# elektrosluch.net
KiCad netlist of a schematic drawn in EAGLE
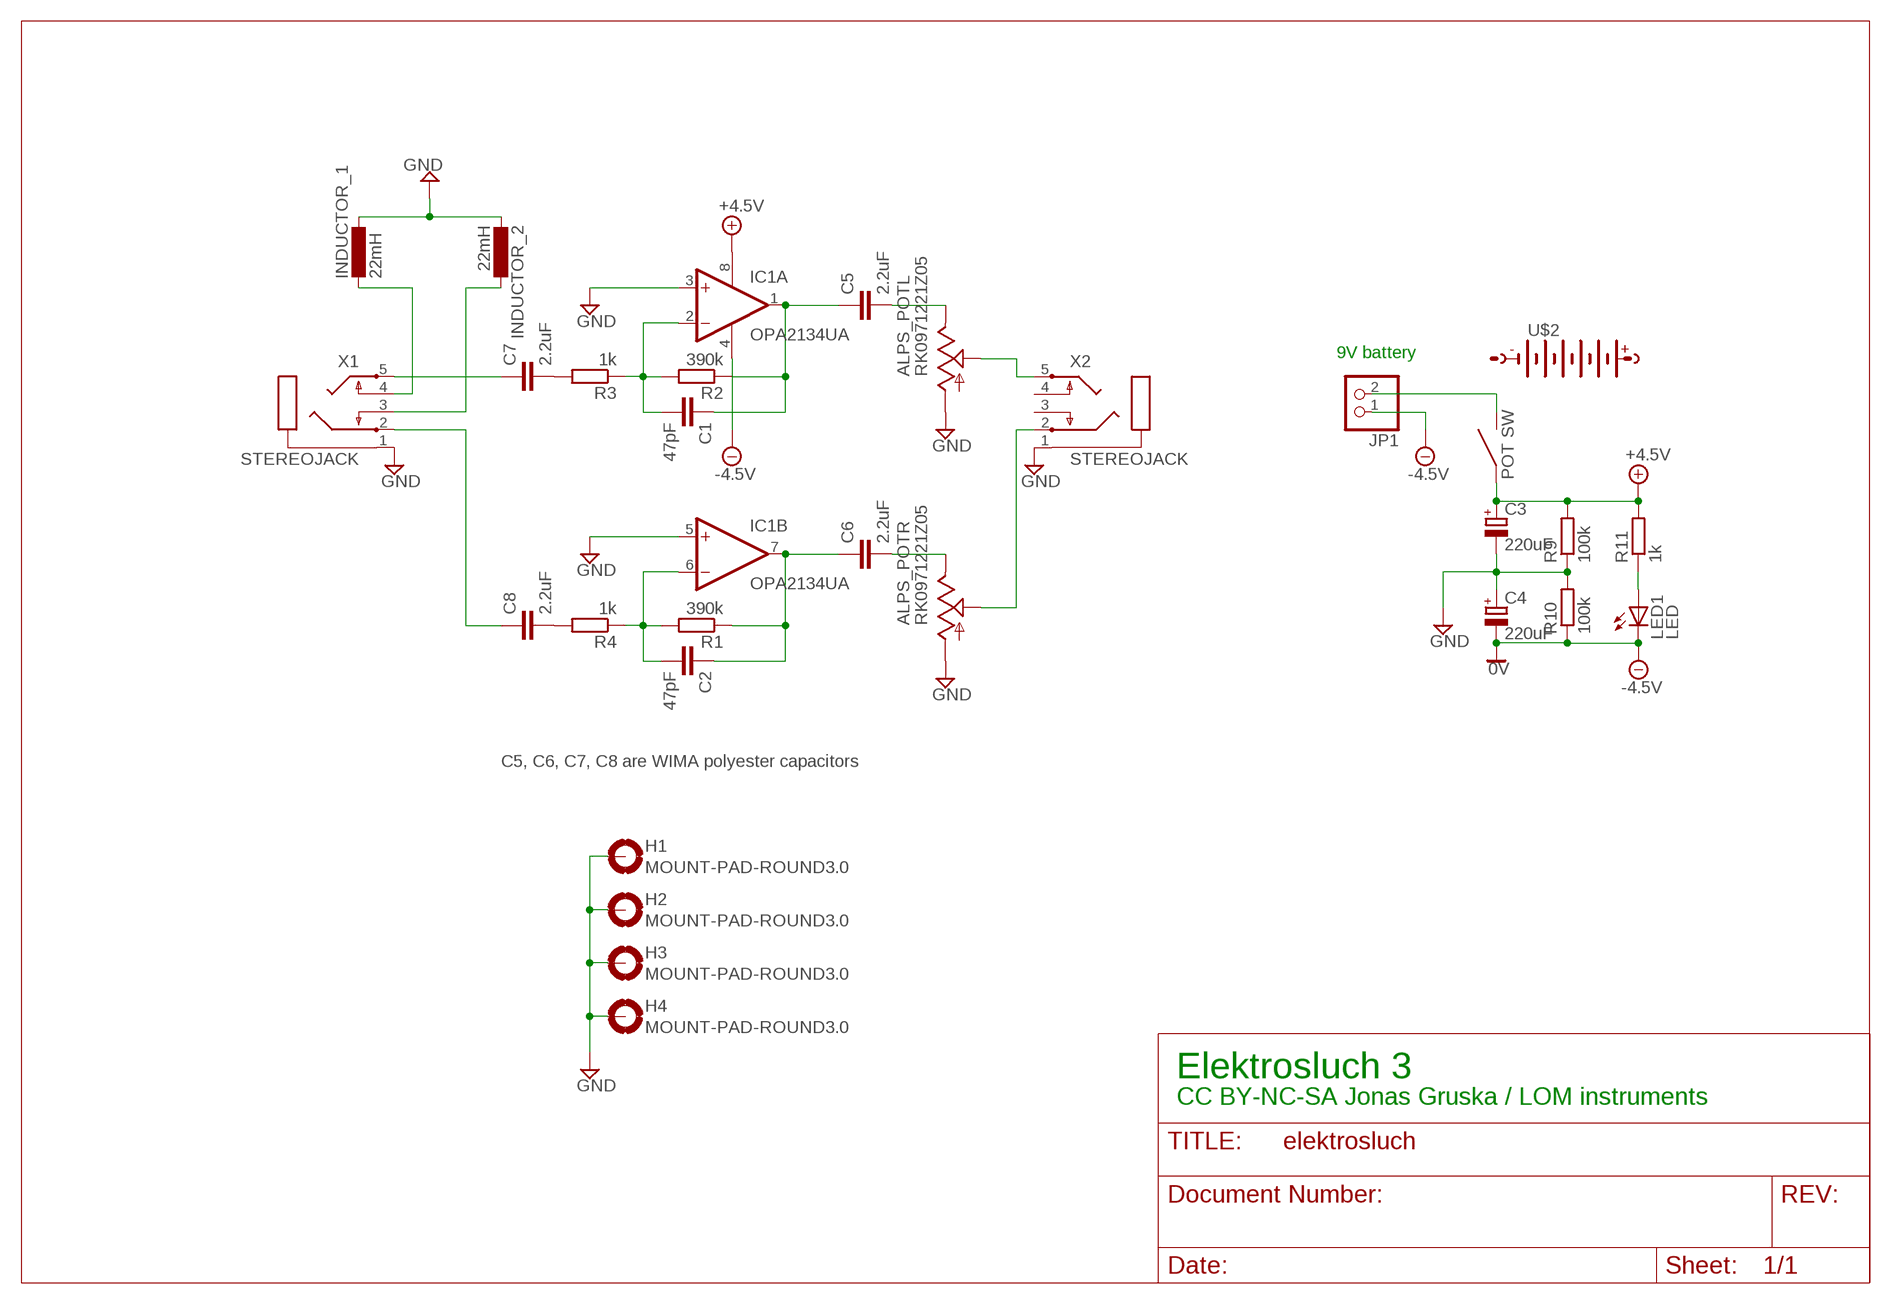
[diagram p0: schematic, sheet 1]

(export (version "E")
  (design (tool "Eeschema 10.0.6"))
  (components
    (comp (ref "ALPS_POT")
      (value "RK0971221Z05")
      (footprint "eagle-import:ALPS_RK0971221Z0X")
      (libsource (lib "eagle-import") (part "ALPS_RK0971221Z0N"))
    )
    (comp (ref "C1")
      (value "47pF")
      (footprint "eagle-import:C0805")
      (libsource (lib "eagle-import") (part "C-EUC0805"))
    )
    (comp (ref "C2")
      (value "47pF")
      (footprint "eagle-import:C0805")
      (libsource (lib "eagle-import") (part "C-EUC0805"))
    )
    (comp (ref "C3")
      (value "220uF")
      (footprint "eagle-import:PANASONIC_D")
      (libsource (lib "eagle-import") (part "CPOL-EUD"))
    )
    (comp (ref "C4")
      (value "220uF")
      (footprint "eagle-import:PANASONIC_D")
      (libsource (lib "eagle-import") (part "CPOL-EUD"))
    )
    (comp (ref "C5")
      (value "2.2uF")
      (footprint "eagle-import:WIMA10UF")
      (libsource (lib "eagle-import") (part "WIMA10UF"))
    )
    (comp (ref "C6")
      (value "2.2uF")
      (footprint "eagle-import:WIMA10UF")
      (libsource (lib "eagle-import") (part "WIMA10UF"))
    )
    (comp (ref "C7")
      (value "2.2uF")
      (footprint "eagle-import:WIMA10UF")
      (libsource (lib "eagle-import") (part "WIMA10UF"))
    )
    (comp (ref "C8")
      (value "2.2uF")
      (footprint "eagle-import:WIMA10UF")
      (libsource (lib "eagle-import") (part "WIMA10UF"))
    )
    (comp (ref "H1")
      (value "MOUNT-PAD-ROUND3.0")
      (footprint "eagle-import:3,0-PAD")
      (libsource (lib "eagle-import") (part "MOUNT-PAD-ROUND3.0"))
    )
    (comp (ref "H2")
      (value "MOUNT-PAD-ROUND3.0")
      (footprint "eagle-import:3,0-PAD")
      (libsource (lib "eagle-import") (part "MOUNT-PAD-ROUND3.0"))
    )
    (comp (ref "H3")
      (value "MOUNT-PAD-ROUND3.0")
      (footprint "eagle-import:3,0-PAD")
      (libsource (lib "eagle-import") (part "MOUNT-PAD-ROUND3.0"))
    )
    (comp (ref "H4")
      (value "MOUNT-PAD-ROUND3.0")
      (footprint "eagle-import:3,0-PAD")
      (libsource (lib "eagle-import") (part "MOUNT-PAD-ROUND3.0"))
    )
    (comp (ref "IC1")
      (value "OPA2134UA")
      (footprint "eagle-import:SO08")
      (libsource (lib "eagle-import") (part "OPA2UA134"))
    )
    (comp (ref "INDUCTOR_1")
      (value "22mH")
      (footprint "eagle-import:COIL")
      (libsource (lib "eagle-import") (part "COIL"))
    )
    (comp (ref "INDUCTOR_2")
      (value "22mH")
      (footprint "eagle-import:COIL")
      (libsource (lib "eagle-import") (part "COIL"))
    )
    (comp (ref "JP1")
      (value "PINHD-1X2")
      (footprint "eagle-import:1X02")
      (libsource (lib "eagle-import") (part "PINHD-1X2"))
    )
    (comp (ref "LED1")
      (value "LED")
      (footprint "eagle-import:LED3MM")
      (libsource (lib "eagle-import") (part "LED"))
    )
    (comp (ref "R1")
      (value "390k")
      (footprint "eagle-import:R0805")
      (libsource (lib "eagle-import") (part "R-EU_R0805"))
    )
    (comp (ref "R2")
      (value "390k")
      (footprint "eagle-import:R0805")
      (libsource (lib "eagle-import") (part "R-EU_R0805"))
    )
    (comp (ref "R3")
      (value "1k")
      (footprint "eagle-import:R0805")
      (libsource (lib "eagle-import") (part "R-EU_R0805"))
    )
    (comp (ref "R4")
      (value "1k")
      (footprint "eagle-import:R0805")
      (libsource (lib "eagle-import") (part "R-EU_R0805"))
    )
    (comp (ref "R9")
      (value "100k")
      (footprint "eagle-import:R0805")
      (libsource (lib "eagle-import") (part "R-EU_R0805"))
    )
    (comp (ref "R10")
      (value "100k")
      (footprint "eagle-import:R0805")
      (libsource (lib "eagle-import") (part "R-EU_R0805"))
    )
    (comp (ref "R11")
      (value "1k")
      (footprint "eagle-import:R0805")
      (libsource (lib "eagle-import") (part "R-EU_R0805"))
    )
    (comp (ref "U$2")
      (value "BATT")
      (footprint "eagle-import:BATT")
      (libsource (lib "eagle-import") (part "BATT"))
    )
    (comp (ref "X1")
      (value "STEREOJACK")
      (footprint "eagle-import:STX3100")
      (libsource (lib "eagle-import") (part "STEREOJACK"))
    )
    (comp (ref "X2")
      (value "STEREOJACK")
      (footprint "eagle-import:STX3100")
      (libsource (lib "eagle-import") (part "STEREOJACK"))
    )
  )
  (nets
    (net (code "1") (name "+4.5V") (class "Default")
      (node (ref "ALPS_POT") (pin "S1") (pinfunction "S1_S1") (pintype "power_in"))
      (node (ref "C3") (pin "+") (pinfunction "+_+") (pintype "passive"))
      (node (ref "IC1") (pin "8") (pinfunction "V+_8") (pintype "power_in"))
      (node (ref "R11") (pin "2") (pinfunction "2_2") (pintype "passive"))
      (node (ref "R9") (pin "2") (pinfunction "2_2") (pintype "passive"))
    )
    (net (code "2") (name "-4.5V") (class "Default")
      (node (ref "C4") (pin "-") (pinfunction "-_-") (pintype "passive"))
      (node (ref "IC1") (pin "4") (pinfunction "V-_4") (pintype "power_in"))
      (node (ref "JP1") (pin "1") (pinfunction "1_1") (pintype "passive"))
      (node (ref "LED1") (pin "K") (pinfunction "C_K") (pintype "passive"))
      (node (ref "R10") (pin "1") (pinfunction "1_1") (pintype "passive"))
    )
    (net (code "3") (name "GND") (class "Default")
      (node (ref "ALPS_POT") (pin "G1") (pinfunction "1_G1") (pintype "passive"))
      (node (ref "ALPS_POT") (pin "G2") (pinfunction "1_G2") (pintype "passive"))
      (node (ref "C3") (pin "-") (pinfunction "-_-") (pintype "passive"))
      (node (ref "C4") (pin "+") (pinfunction "+_+") (pintype "passive"))
      (node (ref "H1") (pin "B3,0") (pinfunction "MOUNT_B3,0") (pintype "passive"))
      (node (ref "H2") (pin "B3,0") (pinfunction "MOUNT_B3,0") (pintype "passive"))
      (node (ref "H3") (pin "B3,0") (pinfunction "MOUNT_B3,0") (pintype "passive"))
      (node (ref "H4") (pin "B3,0") (pinfunction "MOUNT_B3,0") (pintype "passive"))
      (node (ref "IC1") (pin "3") (pinfunction "+IN_3") (pintype "input"))
      (node (ref "IC1") (pin "5") (pinfunction "+IN_5") (pintype "input"))
      (node (ref "INDUCTOR_1") (pin "P$1") (pinfunction "1_P$1") (pintype "passive"))
      (node (ref "INDUCTOR_2") (pin "P$2") (pinfunction "2_P$2") (pintype "passive"))
      (node (ref "R10") (pin "2") (pinfunction "2_2") (pintype "passive"))
      (node (ref "R9") (pin "1") (pinfunction "1_1") (pintype "passive"))
      (node (ref "X1") (pin "1") (pinfunction "1_1") (pintype "passive"))
      (node (ref "X2") (pin "1") (pinfunction "1_1") (pintype "passive"))
    )
    (net (code "4") (name "Net-(ALPS_POT-PadS2)") (class "Default")
      (node (ref "ALPS_POT") (pin "S2") (pinfunction "S2_S2") (pintype "power_in"))
      (node (ref "JP1") (pin "2") (pinfunction "2_2") (pintype "passive"))
    )
    (net (code "5") (name "Net-(ALPS_POTB-2)") (class "Default")
      (node (ref "ALPS_POT") (pin "O1") (pinfunction "2_O1") (pintype "passive"))
      (node (ref "X2") (pin "5") (pinfunction "5_5") (pintype "passive"))
    )
    (net (code "6") (name "Net-(ALPS_POTB-3)") (class "Default")
      (node (ref "ALPS_POT") (pin "I1") (pinfunction "3_I1") (pintype "passive"))
      (node (ref "C5") (pin "P$2") (pinfunction "2_P$2") (pintype "passive"))
    )
    (net (code "7") (name "Net-(ALPS_POTC-2)") (class "Default")
      (node (ref "ALPS_POT") (pin "O2") (pinfunction "2_O2") (pintype "passive"))
      (node (ref "X2") (pin "2") (pinfunction "2_2") (pintype "passive"))
    )
    (net (code "8") (name "Net-(ALPS_POTC-3)") (class "Default")
      (node (ref "ALPS_POT") (pin "I2") (pinfunction "3_I2") (pintype "passive"))
      (node (ref "C6") (pin "P$2") (pinfunction "2_P$2") (pintype "passive"))
    )
    (net (code "9") (name "Net-(C5-1)") (class "Default")
      (node (ref "C1") (pin "1") (pinfunction "1_1") (pintype "passive"))
      (node (ref "C5") (pin "P$1") (pinfunction "1_P$1") (pintype "passive"))
      (node (ref "IC1") (pin "1") (pinfunction "OUT_1") (pintype "output"))
      (node (ref "R2") (pin "1") (pinfunction "1_1") (pintype "passive"))
    )
    (net (code "10") (name "Net-(C6-1)") (class "Default")
      (node (ref "C2") (pin "1") (pinfunction "1_1") (pintype "passive"))
      (node (ref "C6") (pin "P$1") (pinfunction "1_P$1") (pintype "passive"))
      (node (ref "IC1") (pin "7") (pinfunction "OUT_7") (pintype "output"))
      (node (ref "R1") (pin "1") (pinfunction "1_1") (pintype "passive"))
    )
    (net (code "11") (name "Net-(C7-1)") (class "Default")
      (node (ref "C7") (pin "P$1") (pinfunction "1_P$1") (pintype "passive"))
      (node (ref "X1") (pin "5") (pinfunction "5_5") (pintype "passive"))
    )
    (net (code "12") (name "Net-(C7-2)") (class "Default")
      (node (ref "C7") (pin "P$2") (pinfunction "2_P$2") (pintype "passive"))
      (node (ref "R3") (pin "2") (pinfunction "2_2") (pintype "passive"))
    )
    (net (code "13") (name "Net-(C8-1)") (class "Default")
      (node (ref "C8") (pin "P$1") (pinfunction "1_P$1") (pintype "passive"))
      (node (ref "X1") (pin "2") (pinfunction "2_2") (pintype "passive"))
    )
    (net (code "14") (name "Net-(C8-2)") (class "Default")
      (node (ref "C8") (pin "P$2") (pinfunction "2_P$2") (pintype "passive"))
      (node (ref "R4") (pin "2") (pinfunction "2_2") (pintype "passive"))
    )
    (net (code "15") (name "Net-(IC1A--IN)") (class "Default")
      (node (ref "C1") (pin "2") (pinfunction "2_2") (pintype "passive"))
      (node (ref "IC1") (pin "2") (pinfunction "-IN_2") (pintype "input"))
      (node (ref "R2") (pin "2") (pinfunction "2_2") (pintype "passive"))
      (node (ref "R3") (pin "1") (pinfunction "1_1") (pintype "passive"))
    )
    (net (code "16") (name "Net-(IC1B--IN)") (class "Default")
      (node (ref "C2") (pin "2") (pinfunction "2_2") (pintype "passive"))
      (node (ref "IC1") (pin "6") (pinfunction "-IN_6") (pintype "input"))
      (node (ref "R1") (pin "2") (pinfunction "2_2") (pintype "passive"))
      (node (ref "R4") (pin "1") (pinfunction "1_1") (pintype "passive"))
    )
    (net (code "17") (name "Net-(INDUCTOR_1-2)") (class "Default")
      (node (ref "INDUCTOR_1") (pin "P$2") (pinfunction "2_P$2") (pintype "passive"))
      (node (ref "X1") (pin "4") (pinfunction "4_4") (pintype "passive"))
    )
    (net (code "18") (name "Net-(INDUCTOR_2-1)") (class "Default")
      (node (ref "INDUCTOR_2") (pin "P$1") (pinfunction "1_P$1") (pintype "passive"))
      (node (ref "X1") (pin "3") (pinfunction "3_3") (pintype "passive"))
    )
    (net (code "19") (name "Net-(LED1-PadA)") (class "Default")
      (node (ref "LED1") (pin "A") (pinfunction "A_A") (pintype "passive"))
      (node (ref "R11") (pin "1") (pinfunction "1_1") (pintype "passive"))
    )
    (net (code "20") (name "unconnected-(X2-Pad3)") (class "Default")
      (node (ref "X2") (pin "3") (pinfunction "3_3") (pintype "passive"))
    )
    (net (code "21") (name "unconnected-(X2-Pad4)") (class "Default")
      (node (ref "X2") (pin "4") (pinfunction "4_4") (pintype "passive"))
    )
  )
)
